# BME590LEDV1Schematic.net
KiCad netlist of a schematic drawn in Altium Designer
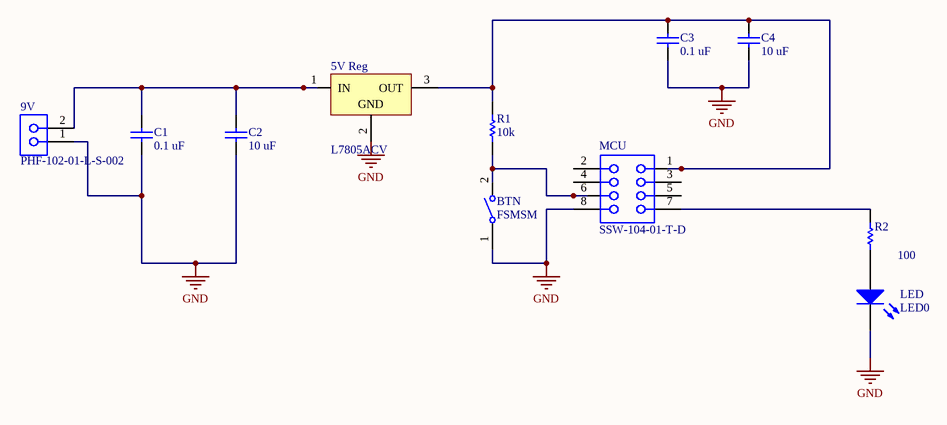
[diagram p0: BME590LEDV1Schematic.SchDoc]

(export (version "E")
  (design (tool "Eeschema 10.0.6"))
  (components
    (comp (ref "5V Reg")
      (value "L7805ACV")
      (footprint "TO220")
      (description "Positive Voltage Regulator, 5V, 3-Pin TO-220")
      (libsource (lib "Integrated_Library - 11.11.18 - 23.08") (part "CMP-0244-00484-1"))
    )
    (comp (ref "9V")
      (value "PHF-102-01-L-S-002")
      (footprint "SMTC-PHF-102-01-X-S-002")
      (description "Press Fit Socket, Through-hole, Vertical, -55 to 125 degC, 2.54 mm Pitch, 2-Pin, Female, RoHS")
      (fields (field (name "MANUFACTURER") "Samtec"))
      (libsource (lib "Integrated_Library - 11.11.18 - 23.35") (part "CMP-1023-00103-1"))
    )
    (comp (ref "BTN")
      (value "FSMSM")
      (footprint "TECO-FSMSM-2_V")
      (description "FSMSM Push Button Switch, 50 mA, -35 to 85 degC, 2-Pin SMD, RoHS, Bulk")
      (fields (field (name "MANUFACTURER") "TE Connectivity"))
      (libsource (lib "Integrated_Library - 11.11.18 - 22.52") (part "CMP-2000-07511-1"))
    )
    (comp (ref "C1")
      (value "0.1 uF")
      (footprint "CAPC2013X70X45NL10T25")
      (description "Chip Capacitor, 10 nF, +/- 10%, 50 V, -55 to 125 degC, 0805 (2012 Metric), RoHS, Tape and Reel")
      (fields (field (name "TOLERANCE") "10%") (field (name "MANUFACTURER") "Murata"))
      (libsource (lib "Integrated_Library - 11.11.18 - 21.55") (part "CMP-2000-05013-1"))
    )
    (comp (ref "C2")
      (value "10 uF")
      (footprint "CAPC2013X70X45NL10T25")
      (description "Chip Capacitor, 10 nF, +/- 10%, 50 V, -55 to 125 degC, 0805 (2012 Metric), RoHS, Tape and Reel")
      (fields (field (name "TOLERANCE") "10%") (field (name "MANUFACTURER") "Murata"))
      (libsource (lib "Integrated_Library - 11.11.18 - 21.55") (part "CMP-2000-05013-1"))
    )
    (comp (ref "C3")
      (value "0.1 uF")
      (footprint "CAPC2013X70X45NL10T25")
      (description "Chip Capacitor, 10 nF, +/- 10%, 50 V, -55 to 125 degC, 0805 (2012 Metric), RoHS, Tape and Reel")
      (fields (field (name "TOLERANCE") "10%") (field (name "MANUFACTURER") "Murata"))
      (libsource (lib "Integrated_Library - 11.11.18 - 21.55") (part "CMP-2000-05013-1"))
    )
    (comp (ref "C4")
      (value "10 uF")
      (footprint "CAPC2013X70X45NL10T25")
      (description "Chip Capacitor, 10 nF, +/- 10%, 50 V, -55 to 125 degC, 0805 (2012 Metric), RoHS, Tape and Reel")
      (fields (field (name "TOLERANCE") "10%") (field (name "MANUFACTURER") "Murata"))
      (libsource (lib "Integrated_Library - 11.11.18 - 21.55") (part "CMP-2000-05013-1"))
    )
    (comp (ref "LED")
      (value "LED0")
      (footprint "LED-0")
      (description "Typical INFRARED GaAs LED")
      (fields (field (name "PUBLISHER") "Altium Limited"))
      (libsource (lib "Miscellaneous Devices") (part "LED0"))
    )
    (comp (ref "MCU")
      (value "SSW-104-01-T-D")
      (footprint "SMTC-SSW-104-01-X-D")
      (description "SQ Post Socket, Through-hole, Vertical, -55 to 105 degC, 2.54mm Pitch, 8-Pin, Female, RoHS")
      (fields (field (name "MANUFACTURER") "Samtec"))
      (libsource (lib "Integrated_Library - 11.11.18 - 23.05") (part "CMP-1023-00339-1"))
    )
    (comp (ref "R1")
      (value "10k")
      (footprint "RESC2013X60X35LL10T20")
      (fields (field (name "MANUFACTURER") "Yageo") (field (name "PART NUMBER") "RT0805FRE0716KL"))
      (libsource (lib "Integrated_Library - 11.11.18 - 21.27") (part "CMP-2001-01501-1"))
    )
    (comp (ref "R2")
      (value "100")
      (footprint "RESC2013X60X35LL10T20")
      (fields (field (name "MANUFACTURER") "Yageo") (field (name "PART NUMBER") "RT0805FRE0716KL"))
      (libsource (lib "Integrated_Library - 11.11.18 - 21.27") (part "CMP-2001-01501-1"))
    )
  )
  (nets
    (net (code "1") (name "GND") (class "Default")
      (node (ref "5V Reg") (pin "2") (pinfunction "GND_2") (pintype "power_in"))
      (node (ref "9V") (pin "1") (pinfunction "1_1") (pintype "passive"))
      (node (ref "BTN") (pin "1") (pinfunction "1_1") (pintype "passive"))
      (node (ref "C1") (pin "1") (pinfunction "1_1") (pintype "passive"))
      (node (ref "C2") (pin "1") (pinfunction "1_1") (pintype "passive"))
      (node (ref "C3") (pin "1") (pinfunction "1_1") (pintype "passive"))
      (node (ref "C4") (pin "1") (pinfunction "1_1") (pintype "passive"))
      (node (ref "LED") (pin "2") (pinfunction "K_2") (pintype "passive"))
      (node (ref "MCU") (pin "8") (pinfunction "8_8") (pintype "passive"))
    )
    (net (code "2") (name "Net-(5V Reg-IN)") (class "Default")
      (node (ref "5V Reg") (pin "1") (pinfunction "IN_1") (pintype "power_in"))
      (node (ref "9V") (pin "2") (pinfunction "2_2") (pintype "passive"))
      (node (ref "C1") (pin "2") (pinfunction "2_2") (pintype "passive"))
      (node (ref "C2") (pin "2") (pinfunction "2_2") (pintype "passive"))
    )
    (net (code "3") (name "Net-(5V Reg-OUT)") (class "Default")
      (node (ref "5V Reg") (pin "3") (pinfunction "OUT_3") (pintype "power_in"))
      (node (ref "C3") (pin "2") (pinfunction "2_2") (pintype "passive"))
      (node (ref "C4") (pin "2") (pinfunction "2_2") (pintype "passive"))
      (node (ref "MCU") (pin "1") (pinfunction "1_1") (pintype "passive"))
      (node (ref "R1") (pin "2") (pinfunction "2_2") (pintype "passive"))
    )
    (net (code "4") (name "Net-(BTN-Pad2)") (class "Default")
      (node (ref "BTN") (pin "2") (pinfunction "2_2") (pintype "passive"))
      (node (ref "MCU") (pin "6") (pinfunction "6_6") (pintype "passive"))
      (node (ref "R1") (pin "1") (pinfunction "1_1") (pintype "passive"))
    )
    (net (code "5") (name "Net-(LED-A)") (class "Default")
      (node (ref "LED") (pin "1") (pinfunction "A_1") (pintype "passive"))
      (node (ref "R2") (pin "1") (pinfunction "1_1") (pintype "passive"))
    )
    (net (code "6") (name "Net-(MCU-Pad7)") (class "Default")
      (node (ref "MCU") (pin "7") (pinfunction "7_7") (pintype "passive"))
      (node (ref "R2") (pin "2") (pinfunction "2_2") (pintype "passive"))
    )
    (net (code "7") (name "unconnected-(MCU-Pad2)") (class "Default")
      (node (ref "MCU") (pin "2") (pinfunction "2_2") (pintype "passive"))
    )
    (net (code "8") (name "unconnected-(MCU-Pad3)") (class "Default")
      (node (ref "MCU") (pin "3") (pinfunction "3_3") (pintype "passive"))
    )
    (net (code "9") (name "unconnected-(MCU-Pad4)") (class "Default")
      (node (ref "MCU") (pin "4") (pinfunction "4_4") (pintype "passive"))
    )
    (net (code "10") (name "unconnected-(MCU-Pad5)") (class "Default")
      (node (ref "MCU") (pin "5") (pinfunction "5_5") (pintype "passive"))
    )
  )
)
